# MCU.net
KiCad netlist of a schematic drawn in Altium Designer
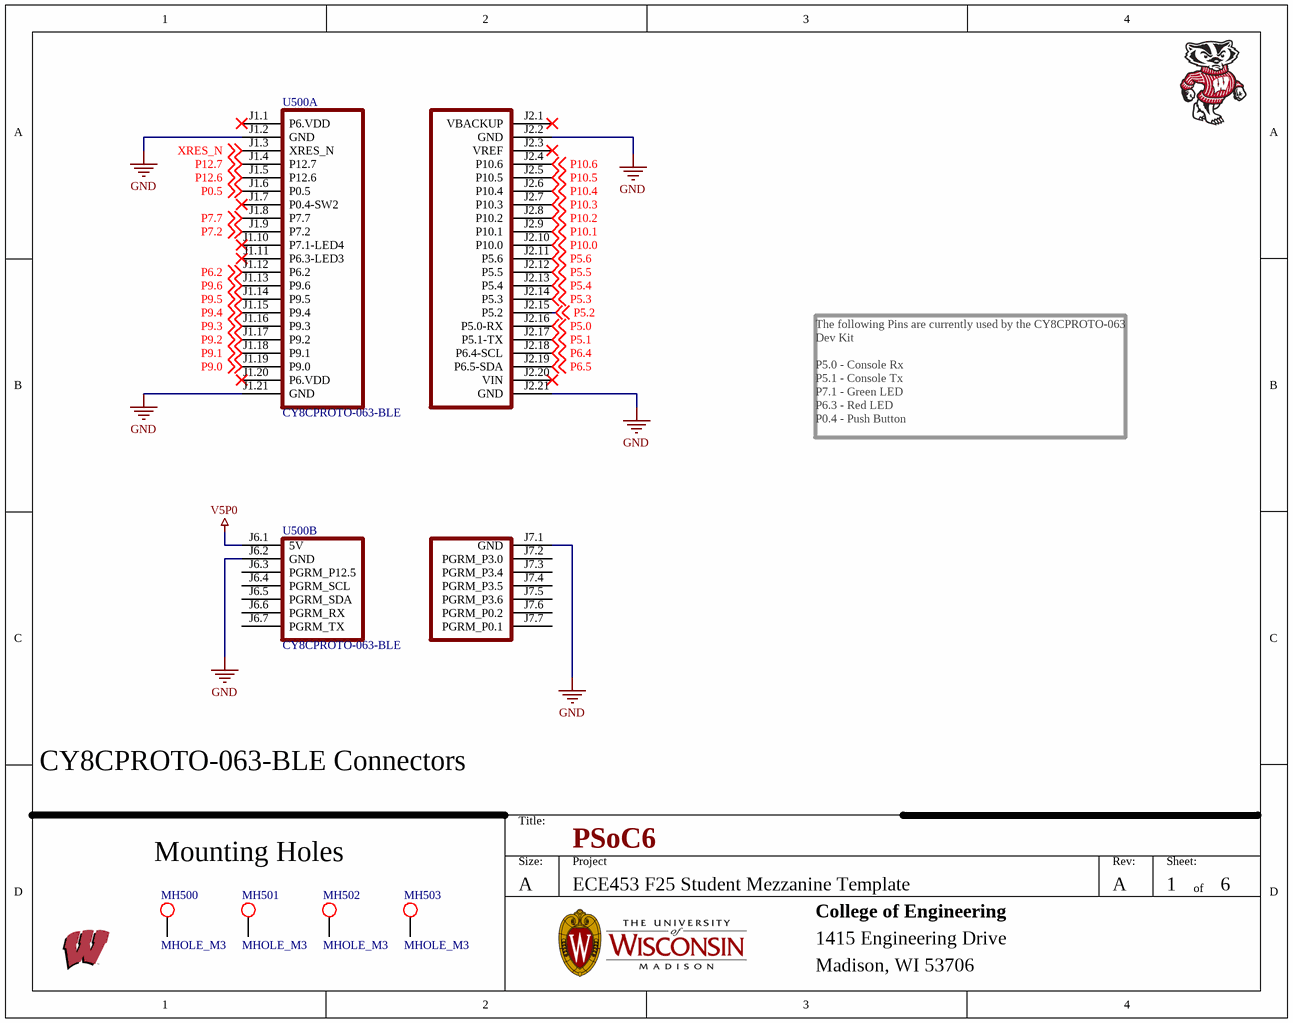
[diagram p0: MCU.SchDoc]

(export (version "E")
  (design (tool "Eeschema 10.0.6"))
  (components
    (comp (ref "MH500")
      (value "MHOLE_M3")
      (footprint "MHOLE_M3")
      (description "Mounting Hole - M3 Metric")
      (libsource (lib "uw-madison-parts") (part "MHOLE_M3"))
    )
    (comp (ref "MH501")
      (value "MHOLE_M3")
      (footprint "MHOLE_M3")
      (description "Mounting Hole - M3 Metric")
      (libsource (lib "uw-madison-parts") (part "MHOLE_M3"))
    )
    (comp (ref "MH502")
      (value "MHOLE_M3")
      (footprint "MHOLE_M3")
      (description "Mounting Hole - M3 Metric")
      (libsource (lib "uw-madison-parts") (part "MHOLE_M3"))
    )
    (comp (ref "MH503")
      (value "MHOLE_M3")
      (footprint "MHOLE_M3")
      (description "Mounting Hole - M3 Metric")
      (libsource (lib "uw-madison-parts") (part "MHOLE_M3"))
    )
    (comp (ref "U500")
      (value "CY8CPROTO-063-BLE")
      (footprint "CY8CPROTO-063-BLE")
      (libsource (lib "ECE453_S24") (part "IC_CY8CPROTO-063-BLE"))
    )
  )
  (nets
    (net (code "1") (name "GND") (class "Default")
      (node (ref "U500") (pin "J1.2") (pinfunction "GND_J1.2") (pintype "passive"))
      (node (ref "U500") (pin "J1.21") (pinfunction "GND_J1.21") (pintype "passive"))
      (node (ref "U500") (pin "J2.2") (pinfunction "GND_J2.2") (pintype "passive"))
      (node (ref "U500") (pin "J2.21") (pinfunction "GND_J2.21") (pintype "passive"))
      (node (ref "U500") (pin "J6.2") (pinfunction "GND_J6.2") (pintype "passive"))
      (node (ref "U500") (pin "J7.1") (pinfunction "GND_J7.1") (pintype "passive"))
    )
    (net (code "2") (name "P0.5") (class "Default")
      (node (ref "U500") (pin "J1.6") (pinfunction "P0.5_J1.6") (pintype "passive"))
    )
    (net (code "3") (name "P5.0") (class "Default")
      (node (ref "U500") (pin "J2.16") (pinfunction "P5.0-RX_J2.16") (pintype "passive"))
    )
    (net (code "4") (name "P5.1") (class "Default")
      (node (ref "U500") (pin "J2.17") (pinfunction "P5.1-TX_J2.17") (pintype "passive"))
    )
    (net (code "5") (name "P5.2") (class "Default")
      (node (ref "U500") (pin "J2.15") (pinfunction "P5.2_J2.15") (pintype "passive"))
    )
    (net (code "6") (name "P5.3") (class "Default")
      (node (ref "U500") (pin "J2.14") (pinfunction "P5.3_J2.14") (pintype "passive"))
    )
    (net (code "7") (name "P5.4") (class "Default")
      (node (ref "U500") (pin "J2.13") (pinfunction "P5.4_J2.13") (pintype "passive"))
    )
    (net (code "8") (name "P5.5") (class "Default")
      (node (ref "U500") (pin "J2.12") (pinfunction "P5.5_J2.12") (pintype "passive"))
    )
    (net (code "9") (name "P5.6") (class "Default")
      (node (ref "U500") (pin "J2.11") (pinfunction "P5.6_J2.11") (pintype "passive"))
    )
    (net (code "10") (name "P6.2") (class "Default")
      (node (ref "U500") (pin "J1.12") (pinfunction "P6.2_J1.12") (pintype "passive"))
    )
    (net (code "11") (name "P6.4") (class "Default")
      (node (ref "U500") (pin "J2.18") (pinfunction "P6.4-SCL_J2.18") (pintype "passive"))
    )
    (net (code "12") (name "P6.5") (class "Default")
      (node (ref "U500") (pin "J2.19") (pinfunction "P6.5-SDA_J2.19") (pintype "passive"))
    )
    (net (code "13") (name "P7.2") (class "Default")
      (node (ref "U500") (pin "J1.9") (pinfunction "P7.2_J1.9") (pintype "passive"))
    )
    (net (code "14") (name "P7.7") (class "Default")
      (node (ref "U500") (pin "J1.8") (pinfunction "P7.7_J1.8") (pintype "passive"))
    )
    (net (code "15") (name "P9.0") (class "Default")
      (node (ref "U500") (pin "J1.19") (pinfunction "P9.0_J1.19") (pintype "passive"))
    )
    (net (code "16") (name "P9.1") (class "Default")
      (node (ref "U500") (pin "J1.18") (pinfunction "P9.1_J1.18") (pintype "passive"))
    )
    (net (code "17") (name "P9.2") (class "Default")
      (node (ref "U500") (pin "J1.17") (pinfunction "P9.2_J1.17") (pintype "passive"))
    )
    (net (code "18") (name "P9.3") (class "Default")
      (node (ref "U500") (pin "J1.16") (pinfunction "P9.3_J1.16") (pintype "passive"))
    )
    (net (code "19") (name "P9.4") (class "Default")
      (node (ref "U500") (pin "J1.15") (pinfunction "P9.4_J1.15") (pintype "passive"))
    )
    (net (code "20") (name "P9.5") (class "Default")
      (node (ref "U500") (pin "J1.14") (pinfunction "P9.5_J1.14") (pintype "passive"))
    )
    (net (code "21") (name "P9.6") (class "Default")
      (node (ref "U500") (pin "J1.13") (pinfunction "P9.6_J1.13") (pintype "passive"))
    )
    (net (code "22") (name "P10.0") (class "Default")
      (node (ref "U500") (pin "J2.10") (pinfunction "P10.0_J2.10") (pintype "passive"))
    )
    (net (code "23") (name "P10.1") (class "Default")
      (node (ref "U500") (pin "J2.9") (pinfunction "P10.1_J2.9") (pintype "passive"))
    )
    (net (code "24") (name "P10.2") (class "Default")
      (node (ref "U500") (pin "J2.8") (pinfunction "P10.2_J2.8") (pintype "passive"))
    )
    (net (code "25") (name "P10.3") (class "Default")
      (node (ref "U500") (pin "J2.7") (pinfunction "P10.3_J2.7") (pintype "passive"))
    )
    (net (code "26") (name "P10.4") (class "Default")
      (node (ref "U500") (pin "J2.6") (pinfunction "P10.4_J2.6") (pintype "passive"))
    )
    (net (code "27") (name "P10.5") (class "Default")
      (node (ref "U500") (pin "J2.5") (pinfunction "P10.5_J2.5") (pintype "passive"))
    )
    (net (code "28") (name "P10.6") (class "Default")
      (node (ref "U500") (pin "J2.4") (pinfunction "P10.6_J2.4") (pintype "passive"))
    )
    (net (code "29") (name "P12.6") (class "Default")
      (node (ref "U500") (pin "J1.5") (pinfunction "P12.6_J1.5") (pintype "passive"))
    )
    (net (code "30") (name "P12.7") (class "Default")
      (node (ref "U500") (pin "J1.4") (pinfunction "P12.7_J1.4") (pintype "passive"))
    )
    (net (code "31") (name "V5P0") (class "Default")
      (node (ref "U500") (pin "J6.1") (pinfunction "5V_J6.1") (pintype "passive"))
    )
    (net (code "32") (name "XRES_N") (class "Default")
      (node (ref "U500") (pin "J1.3") (pinfunction "XRES_N_J1.3") (pintype "passive"))
    )
    (net (code "33") (name "unconnected-(MH500-Pad1)") (class "Default")
      (node (ref "MH500") (pin "1") (pintype "passive"))
    )
    (net (code "34") (name "unconnected-(MH501-Pad1)") (class "Default")
      (node (ref "MH501") (pin "1") (pintype "passive"))
    )
    (net (code "35") (name "unconnected-(MH502-Pad1)") (class "Default")
      (node (ref "MH502") (pin "1") (pintype "passive"))
    )
    (net (code "36") (name "unconnected-(MH503-Pad1)") (class "Default")
      (node (ref "MH503") (pin "1") (pintype "passive"))
    )
    (net (code "37") (name "unconnected-(U500A-P0.4-SW2-PadJ1.7)") (class "Default")
      (node (ref "U500") (pin "J1.7") (pinfunction "P0.4-SW2_J1.7") (pintype "passive+no_connect"))
    )
    (net (code "38") (name "unconnected-(U500A-P6.3-LED3-PadJ1.11)") (class "Default")
      (node (ref "U500") (pin "J1.11") (pinfunction "P6.3-LED3_J1.11") (pintype "passive+no_connect"))
    )
    (net (code "39") (name "unconnected-(U500A-P6.VDD-PadJ1.1)") (class "Default")
      (node (ref "U500") (pin "J1.1") (pinfunction "P6.VDD_J1.1") (pintype "passive+no_connect"))
    )
    (net (code "40") (name "unconnected-(U500A-P6.VDD-PadJ1.20)") (class "Default")
      (node (ref "U500") (pin "J1.20") (pinfunction "P6.VDD_J1.20") (pintype "passive+no_connect"))
    )
    (net (code "41") (name "unconnected-(U500A-P7.1-LED4-PadJ1.10)") (class "Default")
      (node (ref "U500") (pin "J1.10") (pinfunction "P7.1-LED4_J1.10") (pintype "passive+no_connect"))
    )
    (net (code "42") (name "unconnected-(U500A-VBACKUP-PadJ2.1)") (class "Default")
      (node (ref "U500") (pin "J2.1") (pinfunction "VBACKUP_J2.1") (pintype "passive+no_connect"))
    )
    (net (code "43") (name "unconnected-(U500A-VIN-PadJ2.20)") (class "Default")
      (node (ref "U500") (pin "J2.20") (pinfunction "VIN_J2.20") (pintype "passive+no_connect"))
    )
    (net (code "44") (name "unconnected-(U500A-VREF-PadJ2.3)") (class "Default")
      (node (ref "U500") (pin "J2.3") (pinfunction "VREF_J2.3") (pintype "passive+no_connect"))
    )
    (net (code "45") (name "unconnected-(U500B-PGRM_P0.1-PadJ7.7)") (class "Default")
      (node (ref "U500") (pin "J7.7") (pinfunction "PGRM_P0.1_J7.7") (pintype "passive"))
    )
    (net (code "46") (name "unconnected-(U500B-PGRM_P0.2-PadJ7.6)") (class "Default")
      (node (ref "U500") (pin "J7.6") (pinfunction "PGRM_P0.2_J7.6") (pintype "passive"))
    )
    (net (code "47") (name "unconnected-(U500B-PGRM_P3.0-PadJ7.2)") (class "Default")
      (node (ref "U500") (pin "J7.2") (pinfunction "PGRM_P3.0_J7.2") (pintype "passive"))
    )
    (net (code "48") (name "unconnected-(U500B-PGRM_P3.4-PadJ7.3)") (class "Default")
      (node (ref "U500") (pin "J7.3") (pinfunction "PGRM_P3.4_J7.3") (pintype "passive"))
    )
    (net (code "49") (name "unconnected-(U500B-PGRM_P3.5-PadJ7.4)") (class "Default")
      (node (ref "U500") (pin "J7.4") (pinfunction "PGRM_P3.5_J7.4") (pintype "passive"))
    )
    (net (code "50") (name "unconnected-(U500B-PGRM_P3.6-PadJ7.5)") (class "Default")
      (node (ref "U500") (pin "J7.5") (pinfunction "PGRM_P3.6_J7.5") (pintype "passive"))
    )
    (net (code "51") (name "unconnected-(U500B-PGRM_P12.5-PadJ6.3)") (class "Default")
      (node (ref "U500") (pin "J6.3") (pinfunction "PGRM_P12.5_J6.3") (pintype "passive"))
    )
    (net (code "52") (name "unconnected-(U500B-PGRM_RX-PadJ6.6)") (class "Default")
      (node (ref "U500") (pin "J6.6") (pinfunction "PGRM_RX_J6.6") (pintype "passive"))
    )
    (net (code "53") (name "unconnected-(U500B-PGRM_SCL-PadJ6.4)") (class "Default")
      (node (ref "U500") (pin "J6.4") (pinfunction "PGRM_SCL_J6.4") (pintype "passive"))
    )
    (net (code "54") (name "unconnected-(U500B-PGRM_SDA-PadJ6.5)") (class "Default")
      (node (ref "U500") (pin "J6.5") (pinfunction "PGRM_SDA_J6.5") (pintype "passive"))
    )
    (net (code "55") (name "unconnected-(U500B-PGRM_TX-PadJ6.7)") (class "Default")
      (node (ref "U500") (pin "J6.7") (pinfunction "PGRM_TX_J6.7") (pintype "passive"))
    )
  )
)
